# 3V3_Digital_Out.net
KiCad netlist of a schematic drawn in Altium Designer
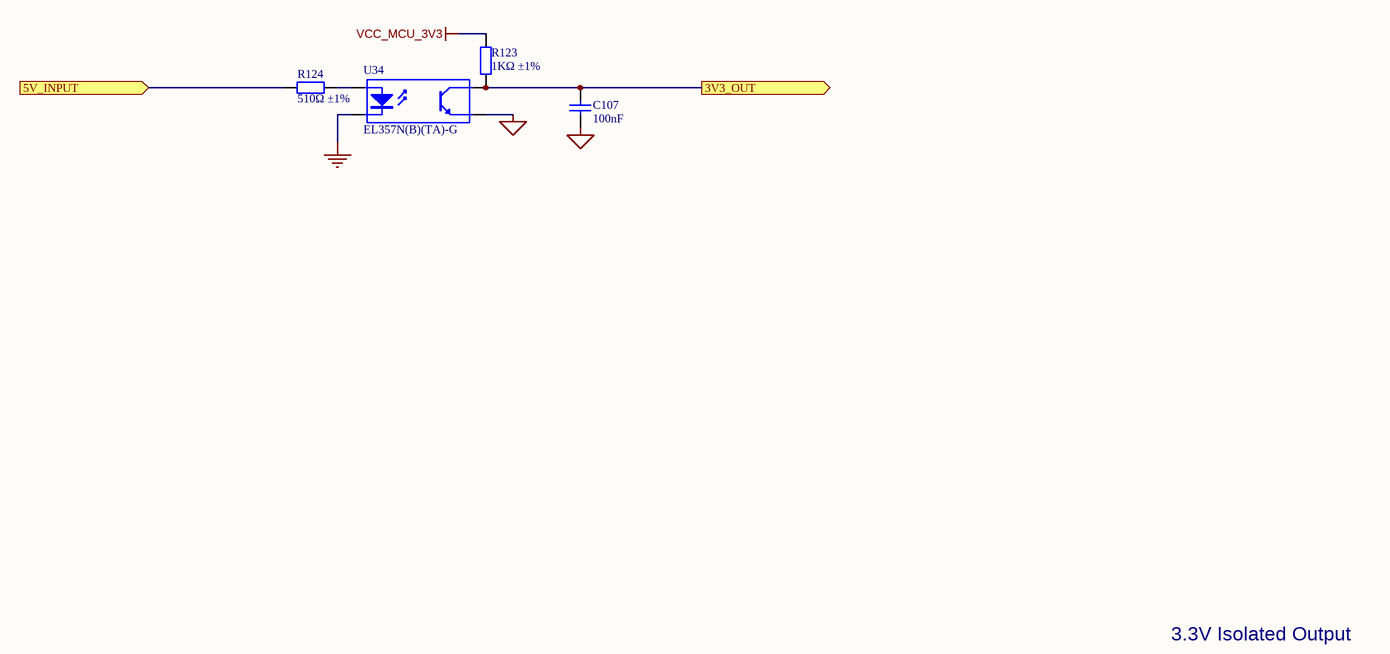
[diagram p0: 3V3_Digital_Out.SchDoc]

(export (version "E")
  (design (tool "Eeschema 10.0.6"))
  (components
    (comp (ref "C107")
      (value "100nF")
      (footprint "0402_C")
      (description "16V 100nF X7R ±10% 0402 Multilayer Ceramic Capacitors MLCC - SMD/SMT ROHS")
      (fields (field (name "MANUFACTURER") "Samsung Electro-Mechanics") (field (name "TOLERANCE") "10%"))
      (libsource (lib "Sienci_Labs") (part "0402 100nF (104) 10% 16V"))
    )
    (comp (ref "R123")
      (value "1KΩ ±1%")
      (footprint "0402_R")
      (description "Chip resistor")
      (fields
        (field (name "MANUFACTURER") "Uniroyal Elec")
        (field (name "MANUFACTURER PART NUMBER") "0402WGF1001TCE")
      )
      (libsource (lib "RES") (part "0402 1K (1001) 1%"))
    )
    (comp (ref "R124")
      (value "510Ω ±1%")
      (footprint "0402_R")
      (description "Chip resistor")
      (fields
        (field (name "MANUFACTURER") "Uniroyal Elec")
        (field (name "MANUFACTURER PART NUMBER") "0402WGF5100TCE")
      )
      (libsource (lib "RES") (part "0402 510R (5100) 1%"))
    )
    (comp (ref "U34")
      (value "EL357N(B)(TA)-G")
      (footprint "SOP-4_P2.54")
      (description "80V 3750V 50mA 0.1V@1mA,20mA 1 6V 1.2V DC SOP-4-2.54mm Optocouplers - Phototransistor Output ROHS")
      (fields (field (name "MANUFACTURER") "Everlight Elec"))
      (libsource (lib "IC") (part "EL357N(B)(TA)-G_[C6649]"))
    )
  )
  (nets
    (net (code "1") (name "/3V3_OUT") (class "Default")
      (node (ref "C107") (pin "2") (pinfunction "2_2") (pintype "passive"))
      (node (ref "R123") (pin "2") (pinfunction "2_2") (pintype "passive"))
      (node (ref "U34") (pin "4") (pinfunction "C_4") (pintype "passive"))
    )
    (net (code "2") (name "/5V_INPUT") (class "Default")
      (node (ref "R124") (pin "1") (pinfunction "1_1") (pintype "passive"))
    )
    (net (code "3") (name "GND") (class "Default")
      (node (ref "U34") (pin "2") (pinfunction "K_2") (pintype "passive"))
    )
    (net (code "4") (name "MCU_GND") (class "Default")
      (node (ref "C107") (pin "1") (pinfunction "1_1") (pintype "passive"))
      (node (ref "U34") (pin "3") (pinfunction "E_3") (pintype "passive"))
    )
    (net (code "5") (name "Net-(U34-A)") (class "Default")
      (node (ref "R124") (pin "2") (pinfunction "2_2") (pintype "passive"))
      (node (ref "U34") (pin "1") (pinfunction "A_1") (pintype "passive"))
    )
    (net (code "6") (name "VCC_MCU_3V3") (class "Default")
      (node (ref "R123") (pin "1") (pinfunction "1_1") (pintype "passive"))
    )
  )
)
